# my_board2.net
KiCad netlist of a schematic drawn in EAGLE
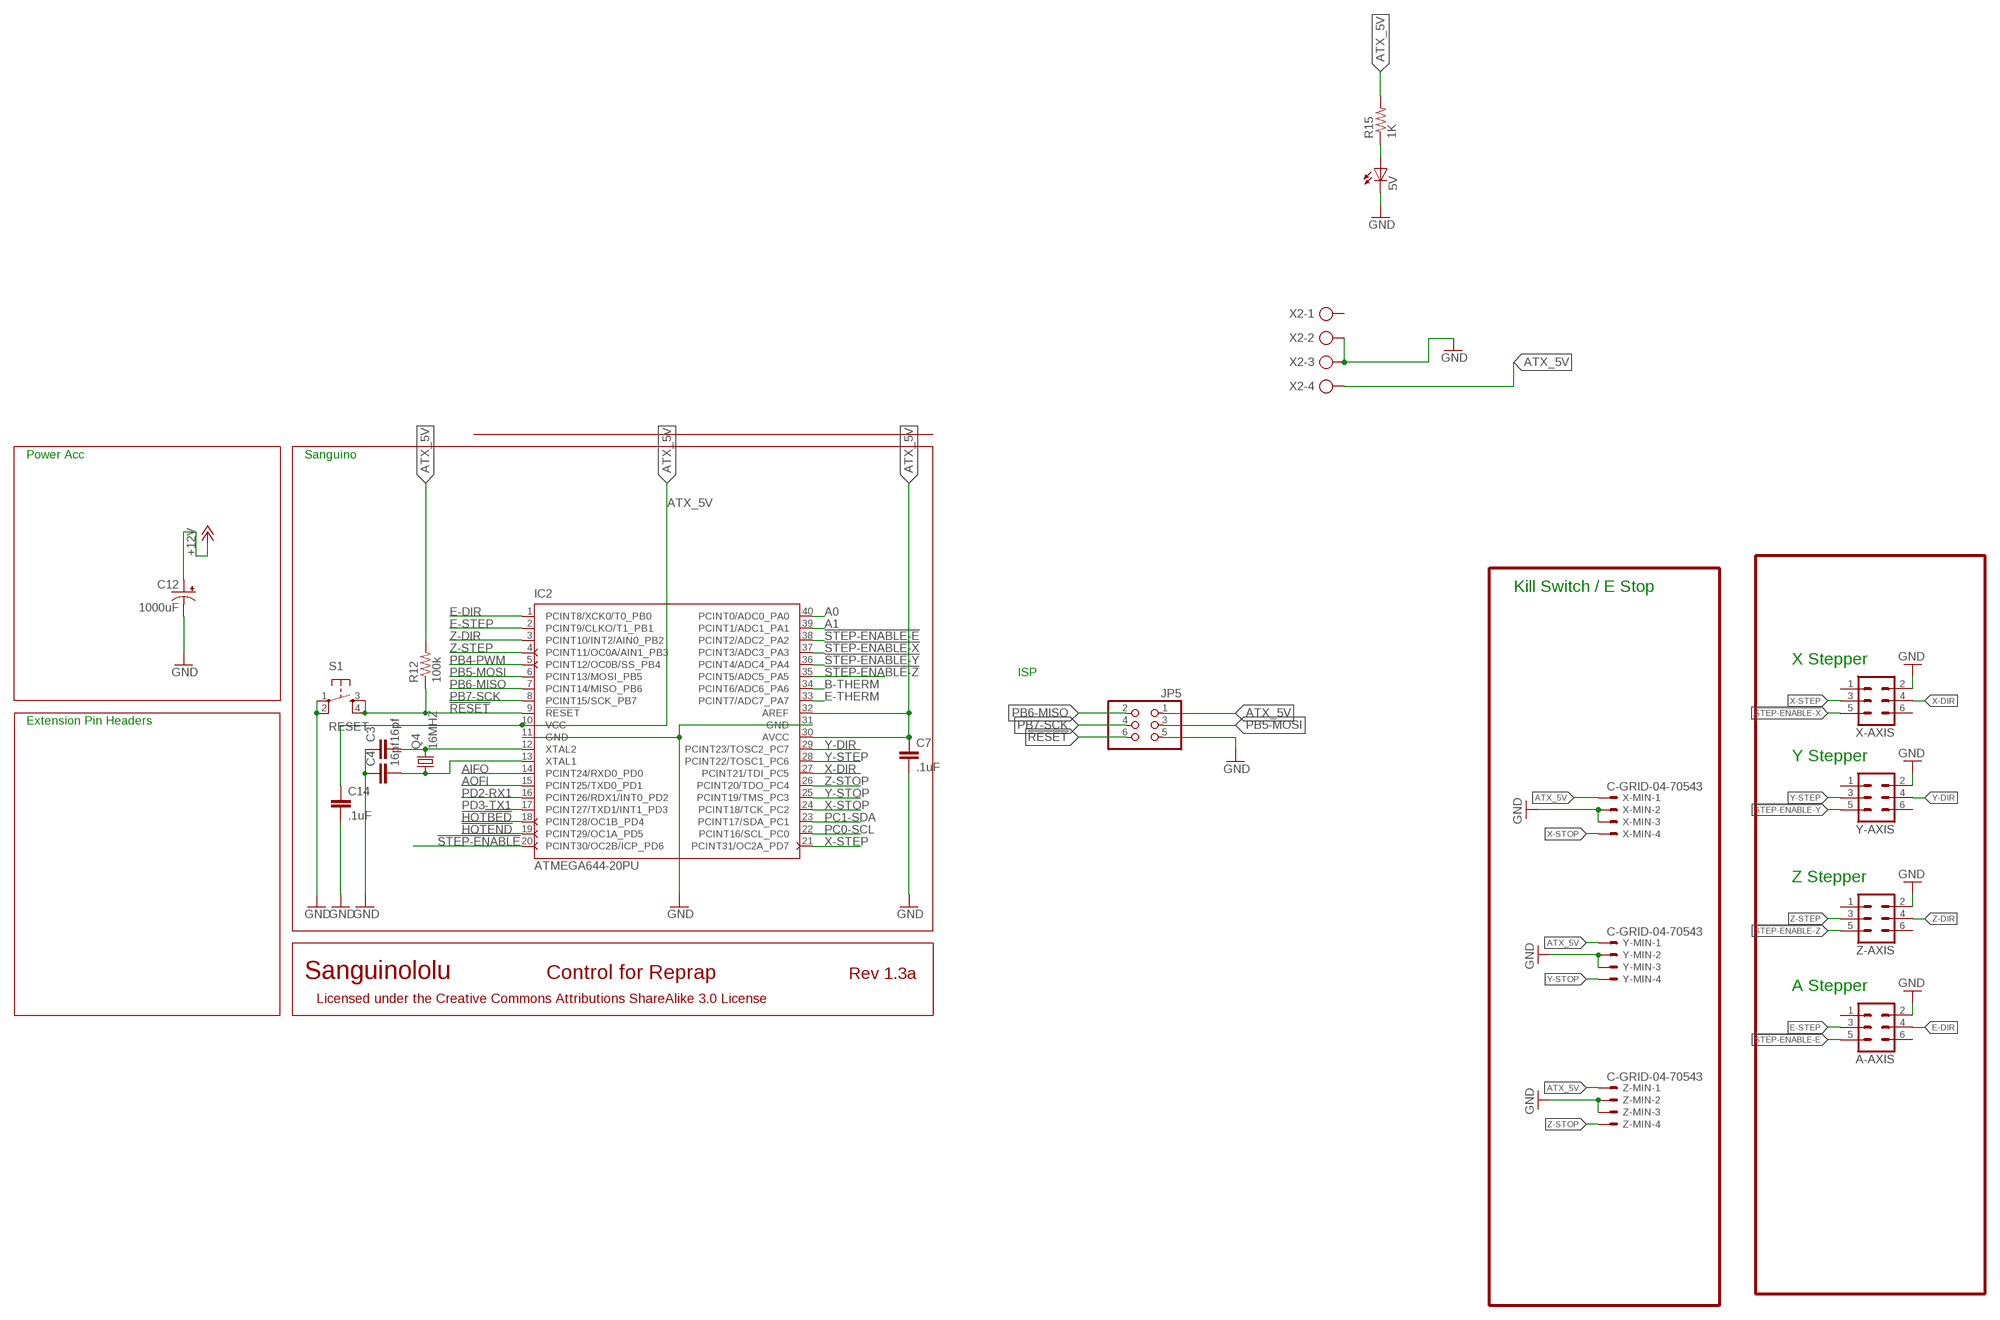
[diagram p0: schematic, sheet 1]

(export (version "E")
  (design (tool "Eeschema 10.0.6"))
  (components
    (comp (ref "5V")
      (value "LED0805")
      (footprint "eagle-import:LED-0805")
      (libsource (lib "eagle-import") (part "LED0805"))
    )
    (comp (ref "A-AXIS")
      (value "ML6")
      (footprint "eagle-import:ML6")
      (libsource (lib "eagle-import") (part "ML6"))
    )
    (comp (ref "C3")
      (value "16pf")
      (footprint "eagle-import:0805")
      (libsource (lib "eagle-import") (part "CAP0805"))
    )
    (comp (ref "C4")
      (value "16pf")
      (footprint "eagle-import:0805")
      (libsource (lib "eagle-import") (part "CAP0805"))
    )
    (comp (ref "C7")
      (value ".1uF")
      (footprint "eagle-import:0805")
      (libsource (lib "eagle-import") (part "CAP0805"))
    )
    (comp (ref "C12")
      (value "1000uF")
      (footprint "eagle-import:CPOL-RADIAL-1000UF-25V")
      (libsource (lib "eagle-import") (part "CAP_POLPTH4"))
    )
    (comp (ref "C14")
      (value ".1uF")
      (footprint "eagle-import:0805")
      (libsource (lib "eagle-import") (part "CAP0805"))
    )
    (comp (ref "IC2")
      (value "ATMEGA644-20PU")
      (footprint "eagle-import:DIL40")
      (libsource (lib "eagle-import") (part "ATMEGA644-PU20"))
    )
    (comp (ref "JP5")
      (value "PINHD-2X3")
      (footprint "eagle-import:2X03")
      (libsource (lib "eagle-import") (part "PINHD-2X3"))
    )
    (comp (ref "Q4")
      (value "16MHZ")
      (footprint "eagle-import:HC49_S")
      (libsource (lib "eagle-import") (part "CRYSTALHC49S"))
    )
    (comp (ref "R12")
      (value "100k")
      (footprint "eagle-import:AXIAL-0.3")
      (libsource (lib "eagle-import") (part "RESISTORPTH1"))
    )
    (comp (ref "R15")
      (value "1K")
      (footprint "eagle-import:0805")
      (libsource (lib "eagle-import") (part "RESISTOR"))
    )
    (comp (ref "S1")
      (value "RESET")
      (footprint "eagle-import:TACTILE-PTH")
      (libsource (lib "eagle-import") (part "TAC_SWITCHPTH"))
    )
    (comp (ref "X-AXIS")
      (value "ML6")
      (footprint "eagle-import:ML6")
      (libsource (lib "eagle-import") (part "ML6"))
    )
    (comp (ref "X-MIN")
      (value "C-GRID-04-70543")
      (footprint "eagle-import:70543-04")
      (libsource (lib "eagle-import") (part "C-GRID-04-70543"))
    )
    (comp (ref "X2")
      (value "AK300/4")
      (footprint "eagle-import:AK300_4")
      (libsource (lib "eagle-import") (part "AK300/4"))
    )
    (comp (ref "Y-AXIS")
      (value "ML6")
      (footprint "eagle-import:ML6")
      (libsource (lib "eagle-import") (part "ML6"))
    )
    (comp (ref "Y-MIN")
      (value "C-GRID-04-70543")
      (footprint "eagle-import:70543-04")
      (libsource (lib "eagle-import") (part "C-GRID-04-70543"))
    )
    (comp (ref "Z-AXIS")
      (value "ML6")
      (footprint "eagle-import:ML6")
      (libsource (lib "eagle-import") (part "ML6"))
    )
    (comp (ref "Z-MIN")
      (value "C-GRID-04-70543")
      (footprint "eagle-import:70543-04")
      (libsource (lib "eagle-import") (part "C-GRID-04-70543"))
    )
  )
  (nets
    (net (code "1") (name "+12V") (class "Default")
      (node (ref "C12") (pin "1") (pinfunction "+_1") (pintype "passive"))
    )
    (net (code "2") (name "/A0") (class "Default")
      (node (ref "IC2") (pin "40") (pinfunction "PCINT0/ADC0_PA0_40") (pintype "bidirectional"))
    )
    (net (code "3") (name "/A1") (class "Default")
      (node (ref "IC2") (pin "39") (pinfunction "PCINT1/ADC1_PA1_39") (pintype "bidirectional"))
    )
    (net (code "4") (name "/AIFO") (class "Default")
      (node (ref "IC2") (pin "14") (pinfunction "PCINT24/RXD0_PD0_14") (pintype "bidirectional"))
    )
    (net (code "5") (name "/AOFI") (class "Default")
      (node (ref "IC2") (pin "15") (pinfunction "PCINT25/TXD0_PD1_15") (pintype "bidirectional"))
    )
    (net (code "6") (name "/B-THERM") (class "Default")
      (node (ref "IC2") (pin "34") (pinfunction "PCINT6/ADC6_PA6_34") (pintype "bidirectional"))
    )
    (net (code "7") (name "/E-THERM") (class "Default")
      (node (ref "IC2") (pin "33") (pinfunction "PCINT7/ADC7_PA7_33") (pintype "bidirectional"))
    )
    (net (code "8") (name "/PB4-PWM") (class "Default")
      (node (ref "IC2") (pin "5") (pinfunction "PCINT12/OC0B/SS_PB4_5") (pintype "bidirectional"))
    )
    (net (code "9") (name "/PC0-SCL") (class "Default")
      (node (ref "IC2") (pin "22") (pinfunction "PCINT16/SCL_PC0_22") (pintype "bidirectional"))
    )
    (net (code "10") (name "/PC1-SDA") (class "Default")
      (node (ref "IC2") (pin "23") (pinfunction "PCINT17/SDA_PC1_23") (pintype "bidirectional"))
    )
    (net (code "11") (name "/PD2-RX1") (class "Default")
      (node (ref "IC2") (pin "16") (pinfunction "PCINT26/RDX1/INT0_PD2_16") (pintype "bidirectional"))
    )
    (net (code "12") (name "/PD3-TX1") (class "Default")
      (node (ref "IC2") (pin "17") (pinfunction "PCINT27/TXD1/INT1_PD3_17") (pintype "bidirectional"))
    )
    (net (code "13") (name "/~{HOTBED}") (class "Default")
      (node (ref "IC2") (pin "18") (pinfunction "PCINT28/OC1B_PD4_18") (pintype "bidirectional"))
    )
    (net (code "14") (name "/~{HOTEND}") (class "Default")
      (node (ref "IC2") (pin "19") (pinfunction "PCINT29/OC1A_PD5_19") (pintype "bidirectional"))
    )
    (net (code "15") (name "/~{RESET}") (class "Default")
      (node (ref "IC2") (pin "9") (pinfunction "~{RESET}_9") (pintype "input"))
      (node (ref "JP5") (pin "6") (pinfunction "6_6") (pintype "passive"))
      (node (ref "R12") (pin "P$1") (pinfunction "1_P$1") (pintype "passive"))
      (node (ref "S1") (pin "3") (pinfunction "3_3") (pintype "passive"))
      (node (ref "S1") (pin "4") (pinfunction "4_4") (pintype "passive"))
    )
    (net (code "16") (name "/~{STEP-ENABLE-E}") (class "Default")
      (node (ref "A-AXIS") (pin "5") (pinfunction "5_5") (pintype "passive"))
      (node (ref "IC2") (pin "38") (pinfunction "PCINT2/ADC2_PA2_38") (pintype "bidirectional"))
    )
    (net (code "17") (name "/~{STEP-ENABLE-X}") (class "Default")
      (node (ref "IC2") (pin "37") (pinfunction "PCINT3/ADC3_PA3_37") (pintype "bidirectional"))
      (node (ref "X-AXIS") (pin "5") (pinfunction "5_5") (pintype "passive"))
    )
    (net (code "18") (name "/~{STEP-ENABLE-Y}") (class "Default")
      (node (ref "IC2") (pin "36") (pinfunction "PCINT4/ADC4_PA4_36") (pintype "bidirectional"))
      (node (ref "Y-AXIS") (pin "5") (pinfunction "5_5") (pintype "passive"))
    )
    (net (code "19") (name "/~{STEP-ENABLE-Z}") (class "Default")
      (node (ref "IC2") (pin "35") (pinfunction "PCINT5/ADC5_PA5_35") (pintype "bidirectional"))
      (node (ref "Z-AXIS") (pin "5") (pinfunction "5_5") (pintype "passive"))
    )
    (net (code "20") (name "/~{STEP-ENABLE}") (class "Default")
      (node (ref "IC2") (pin "20") (pinfunction "PCINT30/OC2B/ICP_PD6_20") (pintype "bidirectional"))
    )
    (net (code "21") (name "ATX_5V") (class "Default")
      (node (ref "C14") (pin "1") (pinfunction "1_1") (pintype "passive"))
      (node (ref "C7") (pin "1") (pinfunction "1_1") (pintype "passive"))
      (node (ref "IC2") (pin "10") (pinfunction "VCC_10") (pintype "power_in"))
      (node (ref "IC2") (pin "30") (pinfunction "AVCC_30") (pintype "power_in"))
      (node (ref "IC2") (pin "32") (pinfunction "AREF_32") (pintype "passive"))
      (node (ref "JP5") (pin "1") (pinfunction "1_1") (pintype "passive"))
      (node (ref "R12") (pin "P$2") (pinfunction "2_P$2") (pintype "passive"))
      (node (ref "R15") (pin "2") (pinfunction "2_2") (pintype "passive"))
      (node (ref "X-MIN") (pin "1") (pinfunction "S_1") (pintype "passive"))
      (node (ref "X2") (pin "4") (pinfunction "KL_4") (pintype "passive"))
      (node (ref "Y-MIN") (pin "1") (pinfunction "S_1") (pintype "passive"))
      (node (ref "Z-MIN") (pin "1") (pinfunction "S_1") (pintype "passive"))
    )
    (net (code "22") (name "E-DIR") (class "Default")
      (node (ref "A-AXIS") (pin "4") (pinfunction "4_4") (pintype "passive"))
      (node (ref "IC2") (pin "1") (pinfunction "PCINT8/XCK0/T0_PB0_1") (pintype "bidirectional"))
    )
    (net (code "23") (name "E-STEP") (class "Default")
      (node (ref "A-AXIS") (pin "3") (pinfunction "3_3") (pintype "passive"))
      (node (ref "IC2") (pin "2") (pinfunction "PCINT9/CLKO/T1_PB1_2") (pintype "bidirectional"))
    )
    (net (code "24") (name "GND") (class "Default")
      (node (ref "5V") (pin "C") (pinfunction "C_C") (pintype "passive"))
      (node (ref "A-AXIS") (pin "2") (pinfunction "2_2") (pintype "passive"))
      (node (ref "C12") (pin "2") (pinfunction "-_2") (pintype "passive"))
      (node (ref "C14") (pin "2") (pinfunction "2_2") (pintype "passive"))
      (node (ref "C3") (pin "1") (pinfunction "1_1") (pintype "passive"))
      (node (ref "C4") (pin "1") (pinfunction "1_1") (pintype "passive"))
      (node (ref "C7") (pin "2") (pinfunction "2_2") (pintype "passive"))
      (node (ref "IC2") (pin "11") (pinfunction "GND_11") (pintype "power_in"))
      (node (ref "IC2") (pin "31") (pinfunction "GND_31") (pintype "power_in"))
      (node (ref "JP5") (pin "5") (pinfunction "5_5") (pintype "passive"))
      (node (ref "S1") (pin "1") (pinfunction "1_1") (pintype "passive"))
      (node (ref "S1") (pin "2") (pinfunction "2_2") (pintype "passive"))
      (node (ref "X-AXIS") (pin "2") (pinfunction "2_2") (pintype "passive"))
      (node (ref "X-MIN") (pin "2") (pinfunction "S_2") (pintype "passive"))
      (node (ref "X-MIN") (pin "3") (pinfunction "S_3") (pintype "passive"))
      (node (ref "X2") (pin "2") (pinfunction "KL_2") (pintype "passive"))
      (node (ref "X2") (pin "3") (pinfunction "KL_3") (pintype "passive"))
      (node (ref "Y-AXIS") (pin "2") (pinfunction "2_2") (pintype "passive"))
      (node (ref "Y-MIN") (pin "2") (pinfunction "S_2") (pintype "passive"))
      (node (ref "Y-MIN") (pin "3") (pinfunction "S_3") (pintype "passive"))
      (node (ref "Z-AXIS") (pin "2") (pinfunction "2_2") (pintype "passive"))
      (node (ref "Z-MIN") (pin "2") (pinfunction "S_2") (pintype "passive"))
      (node (ref "Z-MIN") (pin "3") (pinfunction "S_3") (pintype "passive"))
    )
    (net (code "25") (name "Net-(5V-PadA)") (class "Default")
      (node (ref "5V") (pin "A") (pinfunction "A_A") (pintype "passive"))
      (node (ref "R15") (pin "1") (pinfunction "1_1") (pintype "passive"))
    )
    (net (code "26") (name "Net-(IC2-XTAL1)") (class "Default")
      (node (ref "C4") (pin "2") (pinfunction "2_2") (pintype "passive"))
      (node (ref "IC2") (pin "13") (pinfunction "XTAL1_13") (pintype "input"))
      (node (ref "Q4") (pin "1") (pinfunction "1_1") (pintype "passive"))
    )
    (net (code "27") (name "Net-(IC2-XTAL2)") (class "Default")
      (node (ref "C3") (pin "2") (pinfunction "2_2") (pintype "passive"))
      (node (ref "IC2") (pin "12") (pinfunction "XTAL2_12") (pintype "output"))
      (node (ref "Q4") (pin "2") (pinfunction "2_2") (pintype "passive"))
    )
    (net (code "28") (name "PB5-MOSI") (class "Default")
      (node (ref "IC2") (pin "6") (pinfunction "PCINT13/MOSI_PB5_6") (pintype "bidirectional"))
      (node (ref "JP5") (pin "3") (pinfunction "3_3") (pintype "passive"))
    )
    (net (code "29") (name "PB6-MISO") (class "Default")
      (node (ref "IC2") (pin "7") (pinfunction "PCINT14/MISO_PB6_7") (pintype "bidirectional"))
      (node (ref "JP5") (pin "2") (pinfunction "2_2") (pintype "passive"))
    )
    (net (code "30") (name "PB7-SCK") (class "Default")
      (node (ref "IC2") (pin "8") (pinfunction "PCINT15/SCK_PB7_8") (pintype "bidirectional"))
      (node (ref "JP5") (pin "4") (pinfunction "4_4") (pintype "passive"))
    )
    (net (code "31") (name "X-DIR") (class "Default")
      (node (ref "IC2") (pin "27") (pinfunction "PCINT21/TDI_PC5_27") (pintype "bidirectional"))
      (node (ref "X-AXIS") (pin "4") (pinfunction "4_4") (pintype "passive"))
    )
    (net (code "32") (name "X-STEP") (class "Default")
      (node (ref "IC2") (pin "21") (pinfunction "PCINT31/OC2A_PD7_21") (pintype "bidirectional"))
      (node (ref "X-AXIS") (pin "3") (pinfunction "3_3") (pintype "passive"))
    )
    (net (code "33") (name "X-STOP") (class "Default")
      (node (ref "IC2") (pin "24") (pinfunction "PCINT18/TCK_PC2_24") (pintype "bidirectional"))
      (node (ref "X-MIN") (pin "4") (pinfunction "S_4") (pintype "passive"))
    )
    (net (code "34") (name "Y-DIR") (class "Default")
      (node (ref "IC2") (pin "29") (pinfunction "PCINT23/TOSC2_PC7_29") (pintype "bidirectional"))
      (node (ref "Y-AXIS") (pin "4") (pinfunction "4_4") (pintype "passive"))
    )
    (net (code "35") (name "Y-STEP") (class "Default")
      (node (ref "IC2") (pin "28") (pinfunction "PCINT22/TOSC1_PC6_28") (pintype "bidirectional"))
      (node (ref "Y-AXIS") (pin "3") (pinfunction "3_3") (pintype "passive"))
    )
    (net (code "36") (name "Y-STOP") (class "Default")
      (node (ref "IC2") (pin "25") (pinfunction "PCINT19/TMS_PC3_25") (pintype "bidirectional"))
      (node (ref "Y-MIN") (pin "4") (pinfunction "S_4") (pintype "passive"))
    )
    (net (code "37") (name "Z-DIR") (class "Default")
      (node (ref "IC2") (pin "3") (pinfunction "PCINT10/INT2/AIN0_PB2_3") (pintype "bidirectional"))
      (node (ref "Z-AXIS") (pin "4") (pinfunction "4_4") (pintype "passive"))
    )
    (net (code "38") (name "Z-STEP") (class "Default")
      (node (ref "IC2") (pin "4") (pinfunction "PCINT11/OC0A/AIN1_PB3_4") (pintype "bidirectional"))
      (node (ref "Z-AXIS") (pin "3") (pinfunction "3_3") (pintype "passive"))
    )
    (net (code "39") (name "Z-STOP") (class "Default")
      (node (ref "IC2") (pin "26") (pinfunction "PCINT20/TDO_PC4_26") (pintype "bidirectional"))
      (node (ref "Z-MIN") (pin "4") (pinfunction "S_4") (pintype "passive"))
    )
    (net (code "40") (name "unconnected-(A-AXIS-Pad1)") (class "Default")
      (node (ref "A-AXIS") (pin "1") (pinfunction "1_1") (pintype "passive"))
    )
    (net (code "41") (name "unconnected-(A-AXIS-Pad6)") (class "Default")
      (node (ref "A-AXIS") (pin "6") (pinfunction "6_6") (pintype "passive"))
    )
    (net (code "42") (name "unconnected-(X-AXIS-Pad1)") (class "Default")
      (node (ref "X-AXIS") (pin "1") (pinfunction "1_1") (pintype "passive"))
    )
    (net (code "43") (name "unconnected-(X-AXIS-Pad6)") (class "Default")
      (node (ref "X-AXIS") (pin "6") (pinfunction "6_6") (pintype "passive"))
    )
    (net (code "44") (name "unconnected-(X2A-KL-Pad1)") (class "Default")
      (node (ref "X2") (pin "1") (pinfunction "KL_1") (pintype "passive"))
    )
    (net (code "45") (name "unconnected-(Y-AXIS-Pad1)") (class "Default")
      (node (ref "Y-AXIS") (pin "1") (pinfunction "1_1") (pintype "passive"))
    )
    (net (code "46") (name "unconnected-(Y-AXIS-Pad6)") (class "Default")
      (node (ref "Y-AXIS") (pin "6") (pinfunction "6_6") (pintype "passive"))
    )
    (net (code "47") (name "unconnected-(Z-AXIS-Pad1)") (class "Default")
      (node (ref "Z-AXIS") (pin "1") (pinfunction "1_1") (pintype "passive"))
    )
    (net (code "48") (name "unconnected-(Z-AXIS-Pad6)") (class "Default")
      (node (ref "Z-AXIS") (pin "6") (pinfunction "6_6") (pintype "passive"))
    )
  )
)
